# Printer_Power.net
KiCad netlist of a schematic drawn in EAGLE
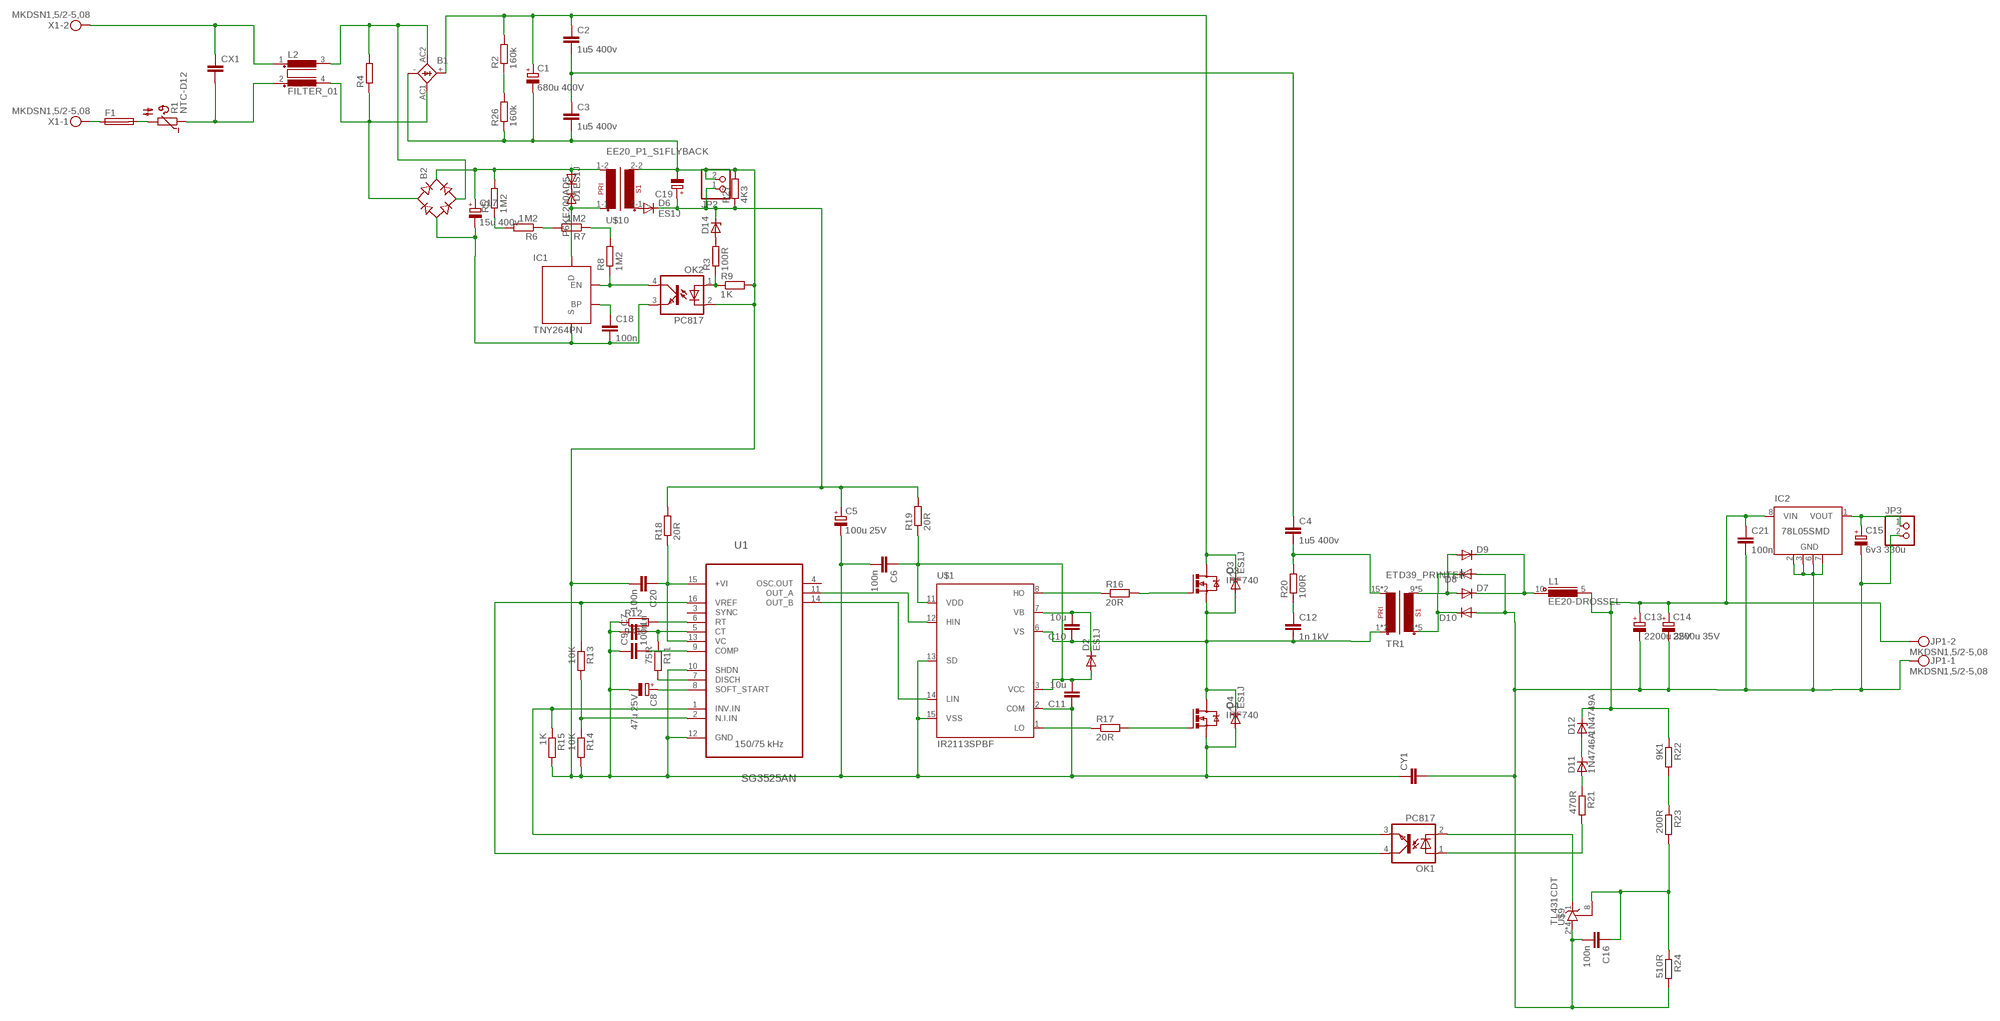
[diagram p0: schematic, sheet 1]

(export (version "E")
  (design (tool "Eeschema 10.0.6"))
  (components
    (comp (ref "B1")
      (value "KBL")
      (footprint "eagle-import:KBL")
      (libsource (lib "eagle-import") (part "KBL"))
    )
    (comp (ref "B2")
      (value "RB1A")
      (footprint "eagle-import:RB1A")
      (libsource (lib "eagle-import") (part "RB1A"))
    )
    (comp (ref "C1")
      (value "680u 400V")
      (footprint "eagle-import:EB35D")
      (libsource (lib "eagle-import") (part "CPOL-EUE10-35"))
    )
    (comp (ref "C2")
      (value "1u5 400v")
      (footprint "eagle-import:C225-074X268")
      (libsource (lib "eagle-import") (part "C-EU225-074X268"))
    )
    (comp (ref "C3")
      (value "1u5 400v")
      (footprint "eagle-import:C225-074X268")
      (libsource (lib "eagle-import") (part "C-EU225-074X268"))
    )
    (comp (ref "C4")
      (value "1u5 400v")
      (footprint "eagle-import:C225-074X268")
      (libsource (lib "eagle-import") (part "C-EU225-074X268"))
    )
    (comp (ref "C5")
      (value "100u 25V")
      (footprint "eagle-import:E2,5-7")
      (libsource (lib "eagle-import") (part "CPOL-EUE2.5-7"))
    )
    (comp (ref "C6")
      (value "100n")
      (footprint "eagle-import:C0805")
      (libsource (lib "eagle-import") (part "C-EUC0805"))
    )
    (comp (ref "C7")
      (value "1n")
      (footprint "eagle-import:C0805")
      (libsource (lib "eagle-import") (part "C-EUC0805"))
    )
    (comp (ref "C8")
      (value "47u 25V")
      (footprint "eagle-import:E2,5-7")
      (libsource (lib "eagle-import") (part "CPOL-EUE2.5-7"))
    )
    (comp (ref "C9")
      (value "100n")
      (footprint "eagle-import:C0805")
      (libsource (lib "eagle-import") (part "C-EUC0805"))
    )
    (comp (ref "C10")
      (value "10u")
      (footprint "eagle-import:C0805")
      (libsource (lib "eagle-import") (part "C-EUC0805"))
    )
    (comp (ref "C11")
      (value "10u")
      (footprint "eagle-import:C0805")
      (libsource (lib "eagle-import") (part "C-EUC0805"))
    )
    (comp (ref "C12")
      (value "1n 1kV")
      (footprint "eagle-import:C050-025X075")
      (libsource (lib "eagle-import") (part "C-EU050-025X075"))
    )
    (comp (ref "C13")
      (value "2200u 35V")
      (footprint "eagle-import:E7,5-18")
      (libsource (lib "eagle-import") (part "CPOL-EUE7.5-18"))
    )
    (comp (ref "C14")
      (value "2200u 35V")
      (footprint "eagle-import:E7,5-18")
      (libsource (lib "eagle-import") (part "CPOL-EUE7.5-18"))
    )
    (comp (ref "C15")
      (value "6v3 330u")
      (footprint "eagle-import:E2,5-7")
      (libsource (lib "eagle-import") (part "CPOL-EUE2.5-7"))
    )
    (comp (ref "C16")
      (value "100n")
      (footprint "eagle-import:C0805")
      (libsource (lib "eagle-import") (part "C-EUC0805"))
    )
    (comp (ref "C17")
      (value "15u 400v")
      (footprint "eagle-import:E5-13")
      (libsource (lib "eagle-import") (part "CPOL-EUE5-13"))
    )
    (comp (ref "C18")
      (value "100n")
      (footprint "eagle-import:C0805")
      (libsource (lib "eagle-import") (part "C-EUC0805"))
    )
    (comp (ref "C19")
      (value "CPOL-EUE2.5-7")
      (footprint "eagle-import:E2,5-7")
      (libsource (lib "eagle-import") (part "CPOL-EUE2.5-7"))
    )
    (comp (ref "C20")
      (value "100n")
      (footprint "eagle-import:C0805")
      (libsource (lib "eagle-import") (part "C-EUC0805"))
    )
    (comp (ref "C21")
      (value "100n")
      (footprint "eagle-import:C0805")
      (libsource (lib "eagle-import") (part "C-EUC0805"))
    )
    (comp (ref "CX1")
      (value "CXXC15B8")
      (footprint "eagle-import:XC15B8")
      (libsource (lib "eagle-import") (part "CXXC15B8"))
    )
    (comp (ref "CY1")
      (value "CYYC10B4")
      (footprint "eagle-import:YC10B4")
      (libsource (lib "eagle-import") (part "CYYC10B4"))
    )
    (comp (ref "D1")
      (value "P6KE200A")
      (footprint "eagle-import:DO204-10")
      (libsource (lib "eagle-import") (part "DIODE-DO204-10"))
    )
    (comp (ref "D2")
      (value "ES1J")
      (footprint "eagle-import:DO214AC")
      (libsource (lib "eagle-import") (part "DIODE-DO214AC"))
    )
    (comp (ref "D3")
      (value "ES1J")
      (footprint "eagle-import:DO214AC")
      (libsource (lib "eagle-import") (part "DIODE-DO214AC"))
    )
    (comp (ref "D4")
      (value "ES1J")
      (footprint "eagle-import:DO214AC")
      (libsource (lib "eagle-import") (part "DIODE-DO214AC"))
    )
    (comp (ref "D5")
      (value "ES1J")
      (footprint "eagle-import:DO214AC")
      (libsource (lib "eagle-import") (part "DIODE-DO214AC"))
    )
    (comp (ref "D6")
      (value "ES1J")
      (footprint "eagle-import:DO214AC")
      (libsource (lib "eagle-import") (part "DIODE-DO214AC"))
    )
    (comp (ref "D7")
      (value "DIODE-DO220S")
      (footprint "eagle-import:DO220S")
      (libsource (lib "eagle-import") (part "DIODE-DO220S"))
    )
    (comp (ref "D8")
      (value "DIODE-DO220S")
      (footprint "eagle-import:DO220S")
      (libsource (lib "eagle-import") (part "DIODE-DO220S"))
    )
    (comp (ref "D9")
      (value "DIODE-DO220S")
      (footprint "eagle-import:DO220S")
      (libsource (lib "eagle-import") (part "DIODE-DO220S"))
    )
    (comp (ref "D10")
      (value "DIODE-DO220S")
      (footprint "eagle-import:DO220S")
      (libsource (lib "eagle-import") (part "DIODE-DO220S"))
    )
    (comp (ref "D11")
      (value "1N4746A")
      (footprint "eagle-import:DO41Z10")
      (libsource (lib "eagle-import") (part "ZENER-DIODEDO41Z10"))
    )
    (comp (ref "D12")
      (value "1N4749A")
      (footprint "eagle-import:DO41Z10")
      (libsource (lib "eagle-import") (part "ZENER-DIODEDO41Z10"))
    )
    (comp (ref "D14")
      (value "ZENER-DIODEDO41Z10")
      (footprint "eagle-import:DO41Z10")
      (libsource (lib "eagle-import") (part "ZENER-DIODEDO41Z10"))
    )
    (comp (ref "F1")
      (value "SH22,5")
      (footprint "eagle-import:SH22,5")
      (fields (field (name "MF") "SCHURTER") (field (name "MPN") "0031.8201"))
      (libsource (lib "eagle-import") (part "SH22,5"))
    )
    (comp (ref "IC1")
      (value "TNY264PN")
      (footprint "eagle-import:DIP-8B")
      (libsource (lib "eagle-import") (part "TNY264PN"))
    )
    (comp (ref "IC2")
      (value "78L05SMD")
      (footprint "eagle-import:SO08")
      (libsource (lib "eagle-import") (part "78LSMD05"))
    )
    (comp (ref "JP1")
      (value "MKDSN1,5/2-5,08")
      (footprint "eagle-import:MKDSN1,5_2-5,08")
      (libsource (lib "eagle-import") (part "MKDSN1,5/2-5,08"))
    )
    (comp (ref "JP2")
      (value "PINHD-1X2")
      (footprint "eagle-import:1X02")
      (libsource (lib "eagle-import") (part "PINHD-1X2"))
    )
    (comp (ref "JP3")
      (value "PINHD-1X2")
      (footprint "eagle-import:1X02")
      (libsource (lib "eagle-import") (part "PINHD-1X2"))
    )
    (comp (ref "L1")
      (value "EE20-DROSSEL")
      (footprint "eagle-import:EE20_DROSSEL")
      (libsource (lib "eagle-import") (part "EE20-DROSSEL"))
    )
    (comp (ref "L2")
      (value "FILTER_01")
      (footprint "eagle-import:82721K")
      (libsource (lib "eagle-import") (part "FILTER_01"))
    )
    (comp (ref "OK1")
      (value "PC817")
      (footprint "eagle-import:DIL04")
      (fields (field (name "MPN") "PC817X4J000F"))
      (libsource (lib "eagle-import") (part "PC817"))
    )
    (comp (ref "OK2")
      (value "PC817")
      (footprint "eagle-import:DIL04")
      (fields (field (name "MPN") "PC817X4J000F"))
      (libsource (lib "eagle-import") (part "PC817"))
    )
    (comp (ref "Q3")
      (value "IRF740")
      (footprint "eagle-import:TO220BV")
      (libsource (lib "eagle-import") (part "IRF740"))
    )
    (comp (ref "Q4")
      (value "IRF740")
      (footprint "eagle-import:TO220BV")
      (libsource (lib "eagle-import") (part "IRF740"))
    )
    (comp (ref "R1")
      (value "NTC-D12")
      (footprint "eagle-import:NTC-D12")
      (libsource (lib "eagle-import") (part "NTC-D12"))
    )
    (comp (ref "R2")
      (value "160k")
      (footprint "eagle-import:0207_10")
      (libsource (lib "eagle-import") (part "R-EU_0207/10"))
    )
    (comp (ref "R3")
      (value "100R")
      (footprint "eagle-import:R0805")
      (libsource (lib "eagle-import") (part "R-EU_R0805"))
    )
    (comp (ref "R4")
      (value "R-EU_0309/10")
      (footprint "eagle-import:0309_10")
      (libsource (lib "eagle-import") (part "R-EU_0309/10"))
    )
    (comp (ref "R5")
      (value "1M2")
      (footprint "eagle-import:R0805")
      (libsource (lib "eagle-import") (part "R-EU_R0805"))
    )
    (comp (ref "R6")
      (value "1M2")
      (footprint "eagle-import:R0805")
      (libsource (lib "eagle-import") (part "R-EU_R0805"))
    )
    (comp (ref "R7")
      (value "1M2")
      (footprint "eagle-import:R0805")
      (libsource (lib "eagle-import") (part "R-EU_R0805"))
    )
    (comp (ref "R8")
      (value "1M2")
      (footprint "eagle-import:R0805")
      (libsource (lib "eagle-import") (part "R-EU_R0805"))
    )
    (comp (ref "R9")
      (value "1K")
      (footprint "eagle-import:R0805")
      (libsource (lib "eagle-import") (part "R-EU_R0805"))
    )
    (comp (ref "R11")
      (value "75R")
      (footprint "eagle-import:R0805")
      (libsource (lib "eagle-import") (part "R-EU_R0805"))
    )
    (comp (ref "R12")
      (value "9K1")
      (footprint "eagle-import:R0805")
      (libsource (lib "eagle-import") (part "R-EU_R0805"))
    )
    (comp (ref "R13")
      (value "10K")
      (footprint "eagle-import:R0805")
      (libsource (lib "eagle-import") (part "R-EU_R0805"))
    )
    (comp (ref "R14")
      (value "10K")
      (footprint "eagle-import:R0805")
      (libsource (lib "eagle-import") (part "R-EU_R0805"))
    )
    (comp (ref "R15")
      (value "1K")
      (footprint "eagle-import:R0805")
      (libsource (lib "eagle-import") (part "R-EU_R0805"))
    )
    (comp (ref "R16")
      (value "20R")
      (footprint "eagle-import:0309_12")
      (libsource (lib "eagle-import") (part "R-EU_0309/12"))
    )
    (comp (ref "R17")
      (value "20R")
      (footprint "eagle-import:0309_12")
      (libsource (lib "eagle-import") (part "R-EU_0309/12"))
    )
    (comp (ref "R18")
      (value "20R")
      (footprint "eagle-import:R2512")
      (libsource (lib "eagle-import") (part "R-EU_R2512"))
    )
    (comp (ref "R19")
      (value "20R")
      (footprint "eagle-import:R2512")
      (libsource (lib "eagle-import") (part "R-EU_R2512"))
    )
    (comp (ref "R20")
      (value "100R")
      (footprint "eagle-import:0617_17")
      (libsource (lib "eagle-import") (part "R-EU_0617/17"))
    )
    (comp (ref "R21")
      (value "470R")
      (footprint "eagle-import:R0805")
      (libsource (lib "eagle-import") (part "R-EU_R0805"))
    )
    (comp (ref "R22")
      (value "9K1")
      (footprint "eagle-import:R0805")
      (libsource (lib "eagle-import") (part "R-EU_R0805"))
    )
    (comp (ref "R23")
      (value "200R")
      (footprint "eagle-import:R0805")
      (libsource (lib "eagle-import") (part "R-EU_R0805"))
    )
    (comp (ref "R24")
      (value "510R")
      (footprint "eagle-import:R0805")
      (libsource (lib "eagle-import") (part "R-EU_R0805"))
    )
    (comp (ref "R26")
      (value "160k")
      (footprint "eagle-import:0207_10")
      (libsource (lib "eagle-import") (part "R-EU_0207/10"))
    )
    (comp (ref "R27")
      (value "4K3")
      (footprint "eagle-import:R0805")
      (libsource (lib "eagle-import") (part "R-EU_R0805"))
    )
    (comp (ref "TR1")
      (value "ETD39_PRINTER")
      (footprint "eagle-import:ETD39_16PIN")
      (libsource (lib "eagle-import") (part "ETD39_PRINTER"))
    )
    (comp (ref "U$1")
      (value "IR2113SPBF")
      (footprint "eagle-import:SO16W")
      (libsource (lib "eagle-import") (part "IR2113SPBF"))
    )
    (comp (ref "U$9")
      (value "TL431CDT")
      (footprint "eagle-import:SO8")
      (libsource (lib "eagle-import") (part "TL431CDT"))
    )
    (comp (ref "U$10")
      (value "EE20_P1_S1FLYBACK")
      (footprint "eagle-import:EE20_P1_S1-REV-4PIN")
      (libsource (lib "eagle-import") (part "EE20_P1_S1FLYBACK"))
    )
    (comp (ref "U1")
      (value "SG3525AN")
      (footprint "eagle-import:DIP254P762X510-16")
      (libsource (lib "eagle-import") (part "SG3525AN"))
    )
    (comp (ref "X1")
      (value "MKDSN1,5/2-5,08")
      (footprint "eagle-import:MKDSN1,5_2-5,08")
      (libsource (lib "eagle-import") (part "MKDSN1,5/2-5,08"))
    )
  )
  (nets
    (net (code "1") (name "Net-(B1-AC1)") (class "Default")
      (node (ref "B1") (pin "AC2") (pinfunction "AC1_AC2") (pintype "passive"))
      (node (ref "B2") (pin "AC2") (pinfunction "AC2_AC2") (pintype "passive"))
      (node (ref "L2") (pin "3") (pinfunction "2_3") (pintype "passive"))
      (node (ref "R4") (pin "2") (pinfunction "2_2") (pintype "passive"))
    )
    (net (code "2") (name "Net-(B1-AC2)") (class "Default")
      (node (ref "B1") (pin "AC1") (pinfunction "AC2_AC1") (pintype "passive"))
      (node (ref "B2") (pin "AC1") (pinfunction "AC1_AC1") (pintype "passive"))
      (node (ref "L2") (pin "4") (pinfunction "4_4") (pintype "passive"))
      (node (ref "R4") (pin "1") (pinfunction "1_1") (pintype "passive"))
    )
    (net (code "3") (name "Net-(B1-Pad+)") (class "Default")
      (node (ref "B1") (pin "+") (pinfunction "+_+") (pintype "passive"))
      (node (ref "C1") (pin "+") (pinfunction "+_+") (pintype "passive"))
      (node (ref "C2") (pin "1") (pinfunction "1_1") (pintype "passive"))
      (node (ref "D3") (pin "C") (pinfunction "C_C") (pintype "passive"))
      (node (ref "Q3") (pin "D") (pinfunction "D_D") (pintype "passive"))
      (node (ref "R2") (pin "2") (pinfunction "2_2") (pintype "passive"))
    )
    (net (code "4") (name "Net-(C2-Pad2)") (class "Default")
      (node (ref "C2") (pin "2") (pinfunction "2_2") (pintype "passive"))
      (node (ref "C3") (pin "1") (pinfunction "1_1") (pintype "passive"))
      (node (ref "C4") (pin "1") (pinfunction "1_1") (pintype "passive"))
    )
    (net (code "5") (name "Net-(C4-Pad2)") (class "Default")
      (node (ref "C4") (pin "2") (pinfunction "2_2") (pintype "passive"))
      (node (ref "R20") (pin "2") (pinfunction "2_2") (pintype "passive"))
      (node (ref "TR1") (pin "15") (pinfunction "P1-2_15") (pintype "passive"))
      (node (ref "TR1") (pin "16") (pinfunction "P1-2_16") (pintype "passive"))
    )
    (net (code "6") (name "Net-(C12-Pad1)") (class "Default")
      (node (ref "C12") (pin "1") (pinfunction "1_1") (pintype "passive"))
      (node (ref "R20") (pin "1") (pinfunction "1_1") (pintype "passive"))
    )
    (net (code "7") (name "Net-(C19-Pad+)") (class "Default")
      (node (ref "C19") (pin "+") (pinfunction "+_+") (pintype "passive"))
      (node (ref "C5") (pin "+") (pinfunction "+_+") (pintype "passive"))
      (node (ref "D14") (pin "C") (pinfunction "C_C") (pintype "passive"))
      (node (ref "D6") (pin "C") (pinfunction "C_C") (pintype "passive"))
      (node (ref "JP2") (pin "1") (pinfunction "1_1") (pintype "passive"))
      (node (ref "R18") (pin "2") (pinfunction "2_2") (pintype "passive"))
      (node (ref "R19") (pin "2") (pinfunction "2_2") (pintype "passive"))
      (node (ref "R27") (pin "1") (pinfunction "1_1") (pintype "passive"))
    )
    (net (code "8") (name "Net-(D1-PadC)") (class "Default")
      (node (ref "D1") (pin "C") (pinfunction "C_C") (pintype "passive"))
      (node (ref "D5") (pin "C") (pinfunction "C_C") (pintype "passive"))
    )
    (net (code "9") (name "Net-(D7-PadA)") (class "Default")
      (node (ref "D7") (pin "A") (pinfunction "A_A") (pintype "passive"))
      (node (ref "D9") (pin "A") (pinfunction "A_A") (pintype "passive"))
      (node (ref "TR1") (pin "10") (pinfunction "S1-2_10") (pintype "passive"))
      (node (ref "TR1") (pin "11") (pinfunction "S1-2_11") (pintype "passive"))
      (node (ref "TR1") (pin "12") (pinfunction "S1-2_12") (pintype "passive"))
      (node (ref "TR1") (pin "13") (pinfunction "S1-2_13") (pintype "passive"))
      (node (ref "TR1") (pin "9") (pinfunction "S1-2_9") (pintype "passive"))
    )
    (net (code "10") (name "Net-(D10-PadC)") (class "Default")
      (node (ref "D10") (pin "C") (pinfunction "C_C") (pintype "passive"))
      (node (ref "D8") (pin "C") (pinfunction "C_C") (pintype "passive"))
      (node (ref "TR1") (pin "4") (pinfunction "S1-1_4") (pintype "passive"))
      (node (ref "TR1") (pin "5") (pinfunction "S1-1_5") (pintype "passive"))
      (node (ref "TR1") (pin "6") (pinfunction "S1-1_6") (pintype "passive"))
      (node (ref "TR1") (pin "7") (pinfunction "S1-1_7") (pintype "passive"))
      (node (ref "TR1") (pin "8") (pinfunction "S1-1_8") (pintype "passive"))
    )
    (net (code "11") (name "Net-(D11-PadA)") (class "Default")
      (node (ref "D11") (pin "A") (pinfunction "A_A") (pintype "passive"))
      (node (ref "R21") (pin "1") (pinfunction "1_1") (pintype "passive"))
    )
    (net (code "12") (name "Net-(D11-PadC)") (class "Default")
      (node (ref "D11") (pin "C") (pinfunction "C_C") (pintype "passive"))
      (node (ref "D12") (pin "A") (pinfunction "A_A") (pintype "passive"))
    )
    (net (code "13") (name "Net-(D14-PadA)") (class "Default")
      (node (ref "D14") (pin "A") (pinfunction "A_A") (pintype "passive"))
      (node (ref "R3") (pin "2") (pinfunction "2_2") (pintype "passive"))
    )
    (net (code "14") (name "Net-(F1-Pad2)") (class "Default")
      (node (ref "F1") (pin "2") (pinfunction "2_2") (pintype "passive"))
      (node (ref "R1") (pin "2") (pinfunction "2_2") (pintype "passive"))
    )
    (net (code "15") (name "Net-(IC1-BP)") (class "Default")
      (node (ref "C18") (pin "1") (pinfunction "1_1") (pintype "passive"))
      (node (ref "IC1") (pin "1") (pinfunction "BP_1") (pintype "input"))
    )
    (net (code "16") (name "Net-(IC1-D)") (class "Default")
      (node (ref "D5") (pin "A") (pinfunction "A_A") (pintype "passive"))
      (node (ref "IC1") (pin "5") (pinfunction "D_5") (pintype "input"))
      (node (ref "U$10") (pin "1-1") (pinfunction "P1-1_1-1") (pintype "passive"))
    )
    (net (code "17") (name "Net-(IC1-EN)") (class "Default")
      (node (ref "IC1") (pin "4") (pinfunction "EN_4") (pintype "input"))
      (node (ref "OK2") (pin "4") (pinfunction "COL_4") (pintype "passive"))
      (node (ref "R8") (pin "1") (pinfunction "1_1") (pintype "passive"))
    )
    (net (code "18") (name "Net-(IC2A-VIN)") (class "Default")
      (node (ref "C13") (pin "+") (pinfunction "+_+") (pintype "passive"))
      (node (ref "C14") (pin "+") (pinfunction "+_+") (pintype "passive"))
      (node (ref "C21") (pin "1") (pinfunction "1_1") (pintype "passive"))
      (node (ref "D12") (pin "C") (pinfunction "C_C") (pintype "passive"))
      (node (ref "IC2") (pin "8") (pinfunction "VIN_8") (pintype "passive"))
      (node (ref "JP1") (pin "2") (pinfunction "KL_2") (pintype "passive"))
      (node (ref "L1") (pin "5") (pinfunction "2_5") (pintype "passive"))
      (node (ref "R22") (pin "1") (pinfunction "1_1") (pintype "passive"))
    )
    (net (code "19") (name "Net-(IC2A-VOUT)") (class "Default")
      (node (ref "C15") (pin "+") (pinfunction "+_+") (pintype "passive"))
      (node (ref "IC2") (pin "1") (pinfunction "VOUT_1") (pintype "output"))
      (node (ref "JP3") (pin "1") (pinfunction "1_1") (pintype "passive"))
    )
    (net (code "20") (name "Net-(JP1A-KL)") (class "Default")
      (node (ref "C13") (pin "-") (pinfunction "-_-") (pintype "passive"))
      (node (ref "C14") (pin "-") (pinfunction "-_-") (pintype "passive"))
      (node (ref "C15") (pin "-") (pinfunction "-_-") (pintype "passive"))
      (node (ref "C16") (pin "2") (pinfunction "2_2") (pintype "passive"))
      (node (ref "C21") (pin "2") (pinfunction "2_2") (pintype "passive"))
      (node (ref "CY1") (pin "2") (pinfunction "2_2") (pintype "passive"))
      (node (ref "D10") (pin "A") (pinfunction "A_A") (pintype "passive"))
      (node (ref "D8") (pin "A") (pinfunction "A_A") (pintype "passive"))
      (node (ref "IC2") (pin "2") (pinfunction "GND_2") (pintype "power_in"))
      (node (ref "IC2") (pin "3") (pinfunction "GND_3") (pintype "power_in"))
      (node (ref "IC2") (pin "6") (pinfunction "GND_6") (pintype "power_in"))
      (node (ref "IC2") (pin "7") (pinfunction "GND_7") (pintype "power_in"))
      (node (ref "JP1") (pin "1") (pinfunction "KL_1") (pintype "passive"))
      (node (ref "JP3") (pin "2") (pinfunction "2_2") (pintype "passive"))
      (node (ref "R24") (pin "2") (pinfunction "2_2") (pintype "passive"))
      (node (ref "U$9") (pin "2") (pinfunction "A_2") (pintype "passive"))
      (node (ref "U$9") (pin "3") (pinfunction "A_3") (pintype "passive"))
      (node (ref "U$9") (pin "6") (pinfunction "A_6") (pintype "passive"))
      (node (ref "U$9") (pin "7") (pinfunction "A_7") (pintype "passive"))
    )
    (net (code "21") (name "Net-(L1-1)") (class "Default")
      (node (ref "D7") (pin "C") (pinfunction "C_C") (pintype "passive"))
      (node (ref "D9") (pin "C") (pinfunction "C_C") (pintype "passive"))
      (node (ref "L1") (pin "10") (pinfunction "1_10") (pintype "passive"))
    )
    (net (code "22") (name "Net-(L2-3)") (class "Default")
      (node (ref "CX1") (pin "2") (pinfunction "2_2") (pintype "passive"))
      (node (ref "L2") (pin "2") (pinfunction "3_2") (pintype "passive"))
      (node (ref "R1") (pin "1") (pinfunction "1_1") (pintype "passive"))
    )
    (net (code "23") (name "Net-(OK1-A)") (class "Default")
      (node (ref "OK1") (pin "1") (pinfunction "A_1") (pintype "passive"))
      (node (ref "R21") (pin "2") (pinfunction "2_2") (pintype "passive"))
    )
    (net (code "24") (name "Net-(OK1-C)") (class "Default")
      (node (ref "OK1") (pin "2") (pinfunction "C_2") (pintype "passive"))
      (node (ref "U$9") (pin "1") (pinfunction "C_1") (pintype "passive"))
    )
    (net (code "25") (name "Net-(OK1-COL)") (class "Default")
      (node (ref "OK1") (pin "4") (pinfunction "COL_4") (pintype "passive"))
      (node (ref "R13") (pin "1") (pinfunction "1_1") (pintype "passive"))
      (node (ref "U1") (pin "16") (pinfunction "VREF_16") (pintype "passive"))
    )
    (net (code "26") (name "Net-(OK1-EMIT)") (class "Default")
      (node (ref "OK1") (pin "3") (pinfunction "EMIT_3") (pintype "passive"))
      (node (ref "R15") (pin "1") (pinfunction "1_1") (pintype "passive"))
      (node (ref "U1") (pin "1") (pinfunction "INV.IN_1") (pintype "input"))
    )
    (net (code "27") (name "Net-(OK2-A)") (class "Default")
      (node (ref "OK2") (pin "1") (pinfunction "A_1") (pintype "passive"))
      (node (ref "R3") (pin "1") (pinfunction "1_1") (pintype "passive"))
      (node (ref "R9") (pin "1") (pinfunction "1_1") (pintype "passive"))
    )
    (net (code "28") (name "Net-(OK2-C)") (class "Default")
      (node (ref "B1") (pin "-") (pinfunction "-_-") (pintype "passive"))
      (node (ref "C1") (pin "-") (pinfunction "-_-") (pintype "passive"))
      (node (ref "C11") (pin "1") (pinfunction "1_1") (pintype "passive"))
      (node (ref "C19") (pin "-") (pinfunction "-_-") (pintype "passive"))
      (node (ref "C20") (pin "2") (pinfunction "2_2") (pintype "passive"))
      (node (ref "C3") (pin "2") (pinfunction "2_2") (pintype "passive"))
      (node (ref "C5") (pin "-") (pinfunction "-_-") (pintype "passive"))
      (node (ref "C6") (pin "2") (pinfunction "2_2") (pintype "passive"))
      (node (ref "C7") (pin "1") (pinfunction "1_1") (pintype "passive"))
      (node (ref "C8") (pin "-") (pinfunction "-_-") (pintype "passive"))
      (node (ref "C9") (pin "1") (pinfunction "1_1") (pintype "passive"))
      (node (ref "CY1") (pin "1") (pinfunction "1_1") (pintype "passive"))
      (node (ref "D4") (pin "A") (pinfunction "A_A") (pintype "passive"))
      (node (ref "JP2") (pin "2") (pinfunction "2_2") (pintype "passive"))
      (node (ref "OK2") (pin "2") (pinfunction "C_2") (pintype "passive"))
      (node (ref "Q4") (pin "S") (pinfunction "S_S") (pintype "passive"))
      (node (ref "R12") (pin "1") (pinfunction "1_1") (pintype "passive"))
      (node (ref "R14") (pin "2") (pinfunction "2_2") (pintype "passive"))
      (node (ref "R15") (pin "2") (pinfunction "2_2") (pintype "passive"))
      (node (ref "R26") (pin "1") (pinfunction "1_1") (pintype "passive"))
      (node (ref "R27") (pin "2") (pinfunction "2_2") (pintype "passive"))
      (node (ref "R9") (pin "2") (pinfunction "2_2") (pintype "passive"))
      (node (ref "U$1") (pin "13") (pinfunction "SD_13") (pintype "input"))
      (node (ref "U$1") (pin "15") (pinfunction "VSS_15") (pintype "power_in"))
      (node (ref "U$1") (pin "2") (pinfunction "COM_2") (pintype "power_in"))
      (node (ref "U$10") (pin "2-2") (pinfunction "S1-2_2-2") (pintype "passive"))
      (node (ref "U1") (pin "10") (pinfunction "SHDN_10") (pintype "input"))
      (node (ref "U1") (pin "12") (pinfunction "GND_12") (pintype "passive"))
    )
    (net (code "29") (name "Net-(OK2-EMIT)") (class "Default")
      (node (ref "B2") (pin "-") (pinfunction "-_-") (pintype "passive"))
      (node (ref "C17") (pin "-") (pinfunction "-_-") (pintype "passive"))
      (node (ref "C18") (pin "2") (pinfunction "2_2") (pintype "passive"))
      (node (ref "IC1") (pin "2") (pinfunction "S_2") (pintype "input"))
      (node (ref "IC1") (pin "3") (pinfunction "S_3") (pintype "input"))
      (node (ref "IC1") (pin "7") (pinfunction "S_7") (pintype "input"))
      (node (ref "IC1") (pin "8") (pinfunction "S_8") (pintype "input"))
      (node (ref "OK2") (pin "3") (pinfunction "EMIT_3") (pintype "passive"))
    )
    (net (code "30") (name "Net-(Q3-PadG)") (class "Default")
      (node (ref "Q3") (pin "G") (pinfunction "G_G") (pintype "passive"))
      (node (ref "R16") (pin "2") (pinfunction "2_2") (pintype "passive"))
    )
    (net (code "31") (name "Net-(Q4-PadG)") (class "Default")
      (node (ref "Q4") (pin "G") (pinfunction "G_G") (pintype "passive"))
      (node (ref "R17") (pin "2") (pinfunction "2_2") (pintype "passive"))
    )
    (net (code "32") (name "Net-(R2-Pad1)") (class "Default")
      (node (ref "R2") (pin "1") (pinfunction "1_1") (pintype "passive"))
      (node (ref "R26") (pin "2") (pinfunction "2_2") (pintype "passive"))
    )
    (net (code "33") (name "Net-(R5-Pad1)") (class "Default")
      (node (ref "R5") (pin "1") (pinfunction "1_1") (pintype "passive"))
      (node (ref "R6") (pin "2") (pinfunction "2_2") (pintype "passive"))
    )
    (net (code "34") (name "Net-(R6-Pad1)") (class "Default")
      (node (ref "R6") (pin "1") (pinfunction "1_1") (pintype "passive"))
      (node (ref "R7") (pin "2") (pinfunction "2_2") (pintype "passive"))
    )
    (net (code "35") (name "Net-(R7-Pad1)") (class "Default")
      (node (ref "R7") (pin "1") (pinfunction "1_1") (pintype "passive"))
      (node (ref "R8") (pin "2") (pinfunction "2_2") (pintype "passive"))
    )
    (net (code "36") (name "Net-(R22-Pad2)") (class "Default")
      (node (ref "R22") (pin "2") (pinfunction "2_2") (pintype "passive"))
      (node (ref "R23") (pin "1") (pinfunction "1_1") (pintype "passive"))
    )
    (net (code "37") (name "Net-(U$1-HIN)") (class "Default")
      (node (ref "U$1") (pin "12") (pinfunction "HIN_12") (pintype "input"))
      (node (ref "U1") (pin "11") (pinfunction "OUT_A_11") (pintype "output"))
    )
    (net (code "38") (name "Net-(U$1-HO)") (class "Default")
      (node (ref "R16") (pin "1") (pinfunction "1_1") (pintype "passive"))
      (node (ref "U$1") (pin "8") (pinfunction "HO_8") (pintype "output"))
    )
    (net (code "39") (name "Net-(U$1-LIN)") (class "Default")
      (node (ref "U$1") (pin "14") (pinfunction "LIN_14") (pintype "input"))
      (node (ref "U1") (pin "14") (pinfunction "OUT_B_14") (pintype "output"))
    )
    (net (code "40") (name "Net-(U$1-LO)") (class "Default")
      (node (ref "R17") (pin "1") (pinfunction "1_1") (pintype "passive"))
      (node (ref "U$1") (pin "1") (pinfunction "LO_1") (pintype "output"))
    )
    (net (code "41") (name "Net-(U$1-VB)") (class "Default")
      (node (ref "C10") (pin "2") (pinfunction "2_2") (pintype "passive"))
      (node (ref "D2") (pin "C") (pinfunction "C_C") (pintype "passive"))
      (node (ref "U$1") (pin "7") (pinfunction "VB_7") (pintype "power_in"))
    )
    (net (code "42") (name "Net-(U$1-VCC)") (class "Default")
      (node (ref "C11") (pin "2") (pinfunction "2_2") (pintype "passive"))
      (node (ref "C6") (pin "1") (pinfunction "1_1") (pintype "passive"))
      (node (ref "D2") (pin "A") (pinfunction "A_A") (pintype "passive"))
      (node (ref "R19") (pin "1") (pinfunction "1_1") (pintype "passive"))
      (node (ref "U$1") (pin "11") (pinfunction "VDD_11") (pintype "power_in"))
      (node (ref "U$1") (pin "3") (pinfunction "VCC_3") (pintype "power_in"))
    )
    (net (code "43") (name "Net-(U$1-VS)") (class "Default")
      (node (ref "C10") (pin "1") (pinfunction "1_1") (pintype "passive"))
      (node (ref "C12") (pin "2") (pinfunction "2_2") (pintype "passive"))
      (node (ref "D3") (pin "A") (pinfunction "A_A") (pintype "passive"))
      (node (ref "D4") (pin "C") (pinfunction "C_C") (pintype "passive"))
      (node (ref "Q3") (pin "S") (pinfunction "S_S") (pintype "passive"))
      (node (ref "Q4") (pin "D") (pinfunction "D_D") (pintype "passive"))
      (node (ref "TR1") (pin "1") (pinfunction "P1-1_1") (pintype "passive"))
      (node (ref "TR1") (pin "2") (pinfunction "P1-1_2") (pintype "passive"))
      (node (ref "U$1") (pin "6") (pinfunction "VS_6") (pintype "power_in"))
    )
    (net (code "44") (name "Net-(U$9-R)") (class "Default")
      (node (ref "C16") (pin "1") (pinfunction "1_1") (pintype "passive"))
      (node (ref "R23") (pin "2") (pinfunction "2_2") (pintype "passive"))
      (node (ref "R24") (pin "1") (pinfunction "1_1") (pintype "passive"))
      (node (ref "U$9") (pin "8") (pinfunction "R_8") (pintype "passive"))
    )
    (net (code "45") (name "Net-(U$10-P1-2)") (class "Default")
      (node (ref "B2") (pin "+") (pinfunction "+_+") (pintype "passive"))
      (node (ref "C17") (pin "+") (pinfunction "+_+") (pintype "passive"))
      (node (ref "D1") (pin "A") (pinfunction "A_A") (pintype "passive"))
      (node (ref "R5") (pin "2") (pinfunction "2_2") (pintype "passive"))
      (node (ref "U$10") (pin "1-2") (pinfunction "P1-2_1-2") (pintype "passive"))
    )
    (net (code "46") (name "Net-(U$10-S1-1)") (class "Default")
      (node (ref "D6") (pin "A") (pinfunction "A_A") (pintype "passive"))
      (node (ref "U$10") (pin "2-1") (pinfunction "S1-1_2-1") (pintype "passive"))
    )
    (net (code "47") (name "Net-(U1-+VI)") (class "Default")
      (node (ref "C20") (pin "1") (pinfunction "1_1") (pintype "passive"))
      (node (ref "R18") (pin "1") (pinfunction "1_1") (pintype "passive"))
      (node (ref "U1") (pin "13") (pinfunction "VC_13") (pintype "passive"))
      (node (ref "U1") (pin "15") (pinfunction "+VI_15") (pintype "power_in"))
    )
    (net (code "48") (name "Net-(U1-COMP)") (class "Default")
      (node (ref "C9") (pin "2") (pinfunction "2_2") (pintype "passive"))
      (node (ref "U1") (pin "9") (pinfunction "COMP_9") (pintype "passive"))
    )
    (net (code "49") (name "Net-(U1-CT)") (class "Default")
      (node (ref "C7") (pin "2") (pinfunction "2_2") (pintype "passive"))
      (node (ref "R11") (pin "1") (pinfunction "1_1") (pintype "passive"))
      (node (ref "U1") (pin "5") (pinfunction "CT_5") (pintype "passive"))
    )
    (net (code "50") (name "Net-(U1-DISCH)") (class "Default")
      (node (ref "R11") (pin "2") (pinfunction "2_2") (pintype "passive"))
      (node (ref "U1") (pin "7") (pinfunction "DISCH_7") (pintype "passive"))
    )
    (net (code "51") (name "Net-(U1-N.I.IN)") (class "Default")
      (node (ref "R13") (pin "2") (pinfunction "2_2") (pintype "passive"))
      (node (ref "R14") (pin "1") (pinfunction "1_1") (pintype "passive"))
      (node (ref "U1") (pin "2") (pinfunction "N.I.IN_2") (pintype "input"))
    )
    (net (code "52") (name "Net-(U1-RT)") (class "Default")
      (node (ref "R12") (pin "2") (pinfunction "2_2") (pintype "passive"))
      (node (ref "U1") (pin "6") (pinfunction "RT_6") (pintype "passive"))
    )
    (net (code "53") (name "Net-(U1-SOFT_START)") (class "Default")
      (node (ref "C8") (pin "+") (pinfunction "+_+") (pintype "passive"))
      (node (ref "U1") (pin "8") (pinfunction "SOFT_START_8") (pintype "passive"))
    )
    (net (code "54") (name "Net-(X1A-KL)") (class "Default")
      (node (ref "F1") (pin "1") (pinfunction "1_1") (pintype "passive"))
      (node (ref "X1") (pin "1") (pinfunction "KL_1") (pintype "passive"))
    )
    (net (code "55") (name "Net-(X1B-KL)") (class "Default")
      (node (ref "CX1") (pin "1") (pinfunction "1_1") (pintype "passive"))
      (node (ref "L2") (pin "1") (pinfunction "1_1") (pintype "passive"))
      (node (ref "X1") (pin "2") (pinfunction "KL_2") (pintype "passive"))
    )
    (net (code "56") (name "unconnected-(U1-OSC.OUT-Pad4)") (class "Default")
      (node (ref "U1") (pin "4") (pinfunction "OSC.OUT_4") (pintype "output"))
    )
    (net (code "57") (name "unconnected-(U1-SYNC-Pad3)") (class "Default")
      (node (ref "U1") (pin "3") (pinfunction "SYNC_3") (pintype "passive"))
    )
  )
)
